# 3_3VRegulator.net
KiCad netlist of a schematic drawn in Altium Designer
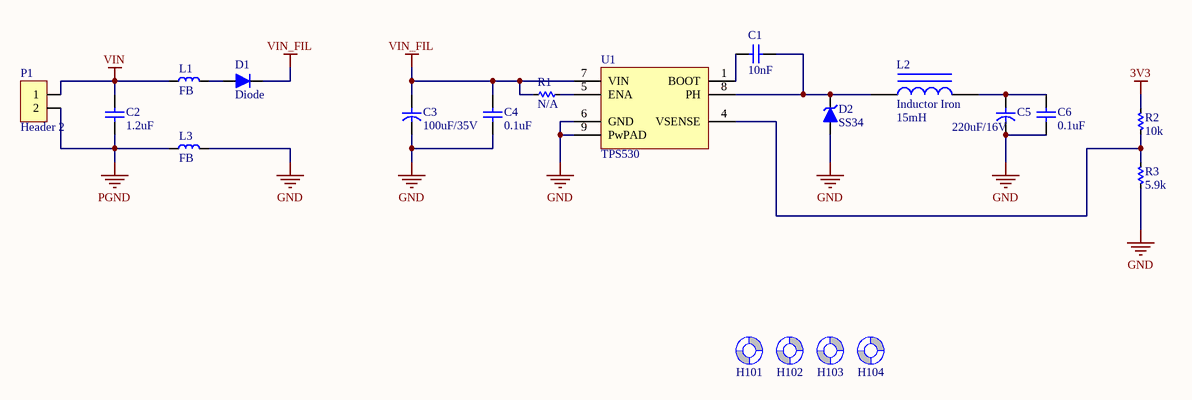
[diagram p0: 3.3VRegulator.SchDoc]

(export (version "E")
  (design (tool "Eeschema 10.0.6"))
  (components
    (comp (ref "C1")
      (value "10nF")
      (footprint "C 0805")
      (description "Capacitor non-pol")
      (libsource (lib "chipfc_libs") (part "Capacitor NP"))
    )
    (comp (ref "C2")
      (value "1.2uF")
      (footprint "C 0805")
      (description "Capacitor non-pol")
      (libsource (lib "chipfc_libs") (part "Capacitor NP"))
    )
    (comp (ref "C3")
      (value "100uF/35V")
      (footprint "C SMD ALU (B)")
      (description "Capacitor pol")
      (libsource (lib "chipfc_libs") (part "Capacitor"))
    )
    (comp (ref "C4")
      (value "0.1uF")
      (footprint "C 0805")
      (description "Capacitor non-pol")
      (libsource (lib "chipfc_libs") (part "Capacitor NP"))
    )
    (comp (ref "C5")
      (value "220uF/16V")
      (footprint "C SMD ALU (B)")
      (description "Capacitor pol")
      (libsource (lib "chipfc_libs") (part "Capacitor"))
    )
    (comp (ref "C6")
      (value "0.1uF")
      (footprint "C 0805")
      (description "Capacitor non-pol")
      (libsource (lib "chipfc_libs") (part "Capacitor NP"))
    )
    (comp (ref "D1")
      (value "Diode")
      (footprint "SOD323")
      (description "Default Diode")
      (libsource (lib "chipfc_libs") (part "Diode"))
    )
    (comp (ref "D2")
      (value "SS34")
      (footprint "DO-214AC (SMA)")
      (description "Zener Diode")
      (libsource (lib "chipfc_libs") (part "Diode Zener"))
    )
    (comp (ref "H101")
      (value "Screw Hole")
      (footprint "SCREW/3.2/7.0/M")
      (libsource (lib "chipfc_libs") (part "Screw Hole"))
    )
    (comp (ref "H102")
      (value "Screw Hole")
      (footprint "SCREW/3.2/7.0/M")
      (libsource (lib "chipfc_libs") (part "Screw Hole"))
    )
    (comp (ref "H103")
      (value "Screw Hole")
      (footprint "SCREW/3.2/7.0/M")
      (libsource (lib "chipfc_libs") (part "Screw Hole"))
    )
    (comp (ref "H104")
      (value "Screw Hole")
      (footprint "SCREW/3.2/7.0/M")
      (libsource (lib "chipfc_libs") (part "Screw Hole"))
    )
    (comp (ref "L1")
      (value "FB")
      (footprint "L 0805 (2012)")
      (description "Inductor")
      (libsource (lib "chipfc_libs") (part "Inductor"))
    )
    (comp (ref "L2")
      (value "Inductor Iron")
      (footprint "AXIAL-0.9")
      (description "Magnetic-Core Inductor")
      (fields (field (name "ALTIUM_VALUE") "15mH") (field (name "PUBLISHER") "Altium Limited"))
      (libsource (lib "Miscellaneous Devices") (part "Inductor Iron"))
    )
    (comp (ref "L3")
      (value "FB")
      (footprint "L 0805 (2012)")
      (description "Inductor")
      (libsource (lib "chipfc_libs") (part "Inductor"))
    )
    (comp (ref "P1")
      (value "Header 2")
      (footprint "HDR/Header/2/BOX/RED")
      (description "Header, 2-Pin")
      (libsource (lib "connectors") (part "Header 2"))
    )
    (comp (ref "R1")
      (value "N/A")
      (footprint "RES-SMD-0201")
      (description "Resistor")
      (fields
        (field (name "MANUFACTURER") "Generic Components")
        (field (name "PUBLISHER") "Altium Hobart Technology Centre")
      )
      (libsource (lib "KhanhBK_SCH_Library_1") (part "Res-SMD"))
    )
    (comp (ref "R2")
      (value "10k")
      (footprint "RES-SMD-0201")
      (description "Resistor")
      (fields
        (field (name "MANUFACTURER") "Generic Components")
        (field (name "PUBLISHER") "Altium Hobart Technology Centre")
      )
      (libsource (lib "KhanhBK_SCH_Library_1") (part "Res-SMD"))
    )
    (comp (ref "R3")
      (value "5.9k")
      (footprint "RES-SMD-0201")
      (description "Resistor")
      (fields
        (field (name "MANUFACTURER") "Generic Components")
        (field (name "PUBLISHER") "Altium Hobart Technology Centre")
      )
      (libsource (lib "KhanhBK_SCH_Library_1") (part "Res-SMD"))
    )
    (comp (ref "U1")
      (value "TPS530")
      (footprint "SOIC-8 EP")
      (description "3/5A, Wide input range, Step-down SWIFT DC-DC Converter")
      (libsource (lib "chipfc_libs") (part "TPS54xx"))
    )
  )
  (nets
    (net (code "1") (name "3V3") (class "Default")
      (node (ref "R2") (pin "2") (pinfunction "2_2") (pintype "passive"))
    )
    (net (code "2") (name "GND") (class "Default")
      (node (ref "C3") (pin "2") (pinfunction "2_2") (pintype "passive"))
      (node (ref "C4") (pin "2") (pinfunction "2_2") (pintype "passive"))
      (node (ref "C5") (pin "2") (pinfunction "2_2") (pintype "passive"))
      (node (ref "C6") (pin "2") (pinfunction "2_2") (pintype "passive"))
      (node (ref "D2") (pin "1") (pinfunction "A_1") (pintype "passive"))
      (node (ref "L3") (pin "2") (pinfunction "2_2") (pintype "passive"))
      (node (ref "R3") (pin "1") (pinfunction "1_1") (pintype "passive"))
      (node (ref "U1") (pin "6") (pinfunction "GND_6") (pintype "passive"))
      (node (ref "U1") (pin "9") (pinfunction "PwPAD_9") (pintype "passive"))
    )
    (net (code "3") (name "Net-(C5-Pad1)") (class "Default")
      (node (ref "C5") (pin "1") (pinfunction "1_1") (pintype "passive"))
      (node (ref "C6") (pin "1") (pinfunction "1_1") (pintype "passive"))
      (node (ref "L2") (pin "2") (pinfunction "2_2") (pintype "passive"))
    )
    (net (code "4") (name "Net-(D1-A)") (class "Default")
      (node (ref "D1") (pin "1") (pinfunction "A_1") (pintype "passive"))
      (node (ref "L1") (pin "2") (pinfunction "2_2") (pintype "passive"))
    )
    (net (code "5") (name "Net-(D2-K)") (class "Default")
      (node (ref "C1") (pin "2") (pinfunction "2_2") (pintype "passive"))
      (node (ref "D2") (pin "2") (pinfunction "K_2") (pintype "passive"))
      (node (ref "L2") (pin "1") (pinfunction "1_1") (pintype "passive"))
      (node (ref "U1") (pin "8") (pinfunction "PH_8") (pintype "passive"))
    )
    (net (code "6") (name "Net-(U1-BOOT)") (class "Default")
      (node (ref "C1") (pin "1") (pinfunction "1_1") (pintype "passive"))
      (node (ref "U1") (pin "1") (pinfunction "BOOT_1") (pintype "passive"))
    )
    (net (code "7") (name "Net-(U1-ENA)") (class "Default")
      (node (ref "R1") (pin "1") (pinfunction "1_1") (pintype "passive"))
      (node (ref "U1") (pin "5") (pinfunction "ENA_5") (pintype "passive"))
    )
    (net (code "8") (name "Net-(U1-VSENSE)") (class "Default")
      (node (ref "R2") (pin "1") (pinfunction "1_1") (pintype "passive"))
      (node (ref "R3") (pin "2") (pinfunction "2_2") (pintype "passive"))
      (node (ref "U1") (pin "4") (pinfunction "VSENSE_4") (pintype "passive"))
    )
    (net (code "9") (name "PGND") (class "Default")
      (node (ref "C2") (pin "2") (pinfunction "2_2") (pintype "passive"))
      (node (ref "L3") (pin "1") (pinfunction "1_1") (pintype "passive"))
      (node (ref "P1") (pin "2") (pinfunction "2_2") (pintype "passive"))
    )
    (net (code "10") (name "VIN") (class "Default")
      (node (ref "C2") (pin "1") (pinfunction "1_1") (pintype "passive"))
      (node (ref "L1") (pin "1") (pinfunction "1_1") (pintype "passive"))
      (node (ref "P1") (pin "1") (pinfunction "1_1") (pintype "passive"))
    )
    (net (code "11") (name "VIN_FIL") (class "Default")
      (node (ref "C3") (pin "1") (pinfunction "1_1") (pintype "passive"))
      (node (ref "C4") (pin "1") (pinfunction "1_1") (pintype "passive"))
      (node (ref "D1") (pin "2") (pinfunction "K_2") (pintype "passive"))
      (node (ref "R1") (pin "2") (pinfunction "2_2") (pintype "passive"))
      (node (ref "U1") (pin "7") (pinfunction "VIN_7") (pintype "passive"))
    )
    (net (code "12") (name "unconnected-(H101-Screw-Pad1)") (class "Default")
      (node (ref "H101") (pin "1") (pinfunction "Screw_1") (pintype "passive"))
    )
    (net (code "13") (name "unconnected-(H102-Screw-Pad1)") (class "Default")
      (node (ref "H102") (pin "1") (pinfunction "Screw_1") (pintype "passive"))
    )
    (net (code "14") (name "unconnected-(H103-Screw-Pad1)") (class "Default")
      (node (ref "H103") (pin "1") (pinfunction "Screw_1") (pintype "passive"))
    )
    (net (code "15") (name "unconnected-(H104-Screw-Pad1)") (class "Default")
      (node (ref "H104") (pin "1") (pinfunction "Screw_1") (pintype "passive"))
    )
  )
)
